# Arduino101BiomedDevBoard.net
KiCad netlist of a schematic drawn in EAGLE
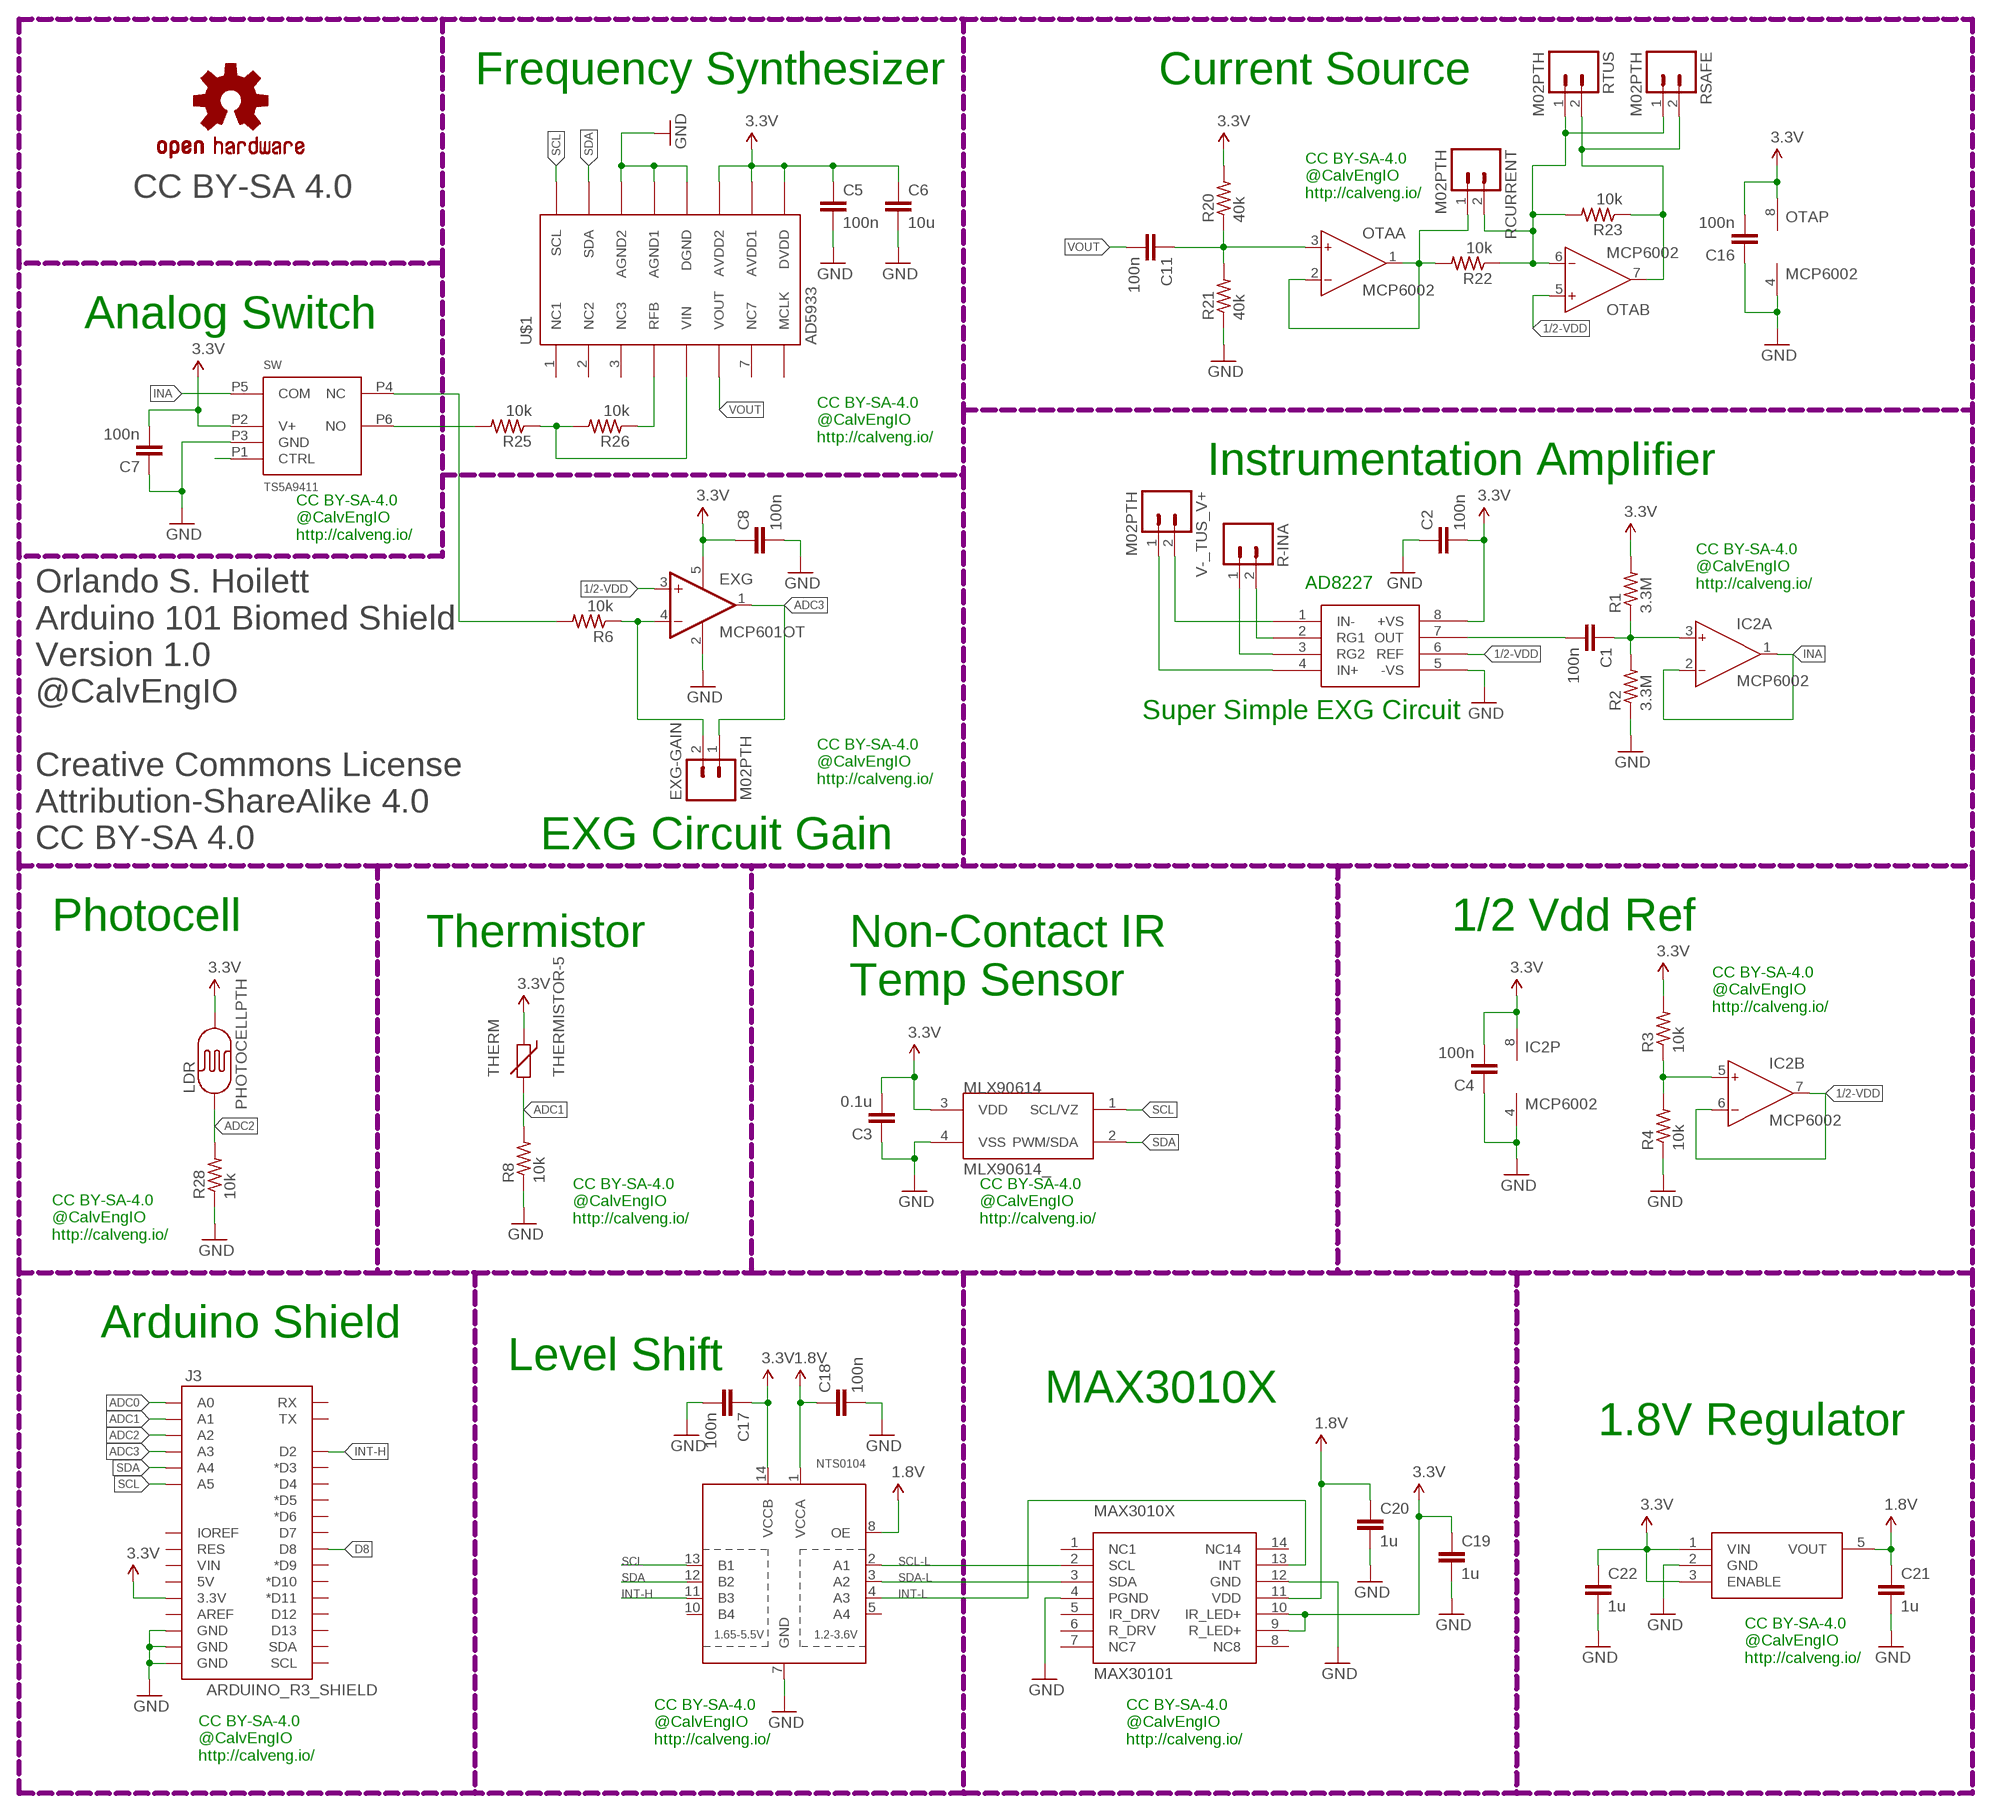
[diagram p0: schematic, sheet 1]

(export (version "E")
  (design (tool "Eeschema 10.0.6"))
  (components
    (comp (ref "1.8V")
      (value "MIC5504")
      (footprint "eagle-import:SOT23-5")
      (libsource (lib "eagle-import") (part "MIC5504"))
    )
    (comp (ref "C1")
      (value "100n")
      (footprint "eagle-import:C0402")
      (libsource (lib "eagle-import") (part "C-EUC0402"))
    )
    (comp (ref "C2")
      (value "100n")
      (footprint "eagle-import:C0402")
      (libsource (lib "eagle-import") (part "C-EUC0402"))
    )
    (comp (ref "C3")
      (value "0.1u")
      (footprint "eagle-import:C0402")
      (libsource (lib "eagle-import") (part "C-EUC0402"))
    )
    (comp (ref "C4")
      (value "100n")
      (footprint "eagle-import:C0402")
      (libsource (lib "eagle-import") (part "C-EUC0402"))
    )
    (comp (ref "C5")
      (value "100n")
      (footprint "eagle-import:C0402")
      (libsource (lib "eagle-import") (part "C-EUC0402"))
    )
    (comp (ref "C6")
      (value "10u")
      (footprint "eagle-import:C0805")
      (libsource (lib "eagle-import") (part "C-EUC0805"))
    )
    (comp (ref "C7")
      (value "100n")
      (footprint "eagle-import:C0402")
      (libsource (lib "eagle-import") (part "C-EUC0402"))
    )
    (comp (ref "C8")
      (value "100n")
      (footprint "eagle-import:C0402")
      (libsource (lib "eagle-import") (part "C-EUC0402"))
    )
    (comp (ref "C11")
      (value "100n")
      (footprint "eagle-import:C0402")
      (libsource (lib "eagle-import") (part "C-EUC0402"))
    )
    (comp (ref "C16")
      (value "100n")
      (footprint "eagle-import:C0402")
      (libsource (lib "eagle-import") (part "C-EUC0402"))
    )
    (comp (ref "C17")
      (value "100n")
      (footprint "eagle-import:C0402")
      (libsource (lib "eagle-import") (part "C-EUC0402"))
    )
    (comp (ref "C18")
      (value "100n")
      (footprint "eagle-import:C0402")
      (libsource (lib "eagle-import") (part "C-EUC0402"))
    )
    (comp (ref "C19")
      (value "1u")
      (footprint "eagle-import:C0402")
      (libsource (lib "eagle-import") (part "C-EUC0402"))
    )
    (comp (ref "C20")
      (value "1u")
      (footprint "eagle-import:C0402")
      (libsource (lib "eagle-import") (part "C-EUC0402"))
    )
    (comp (ref "C21")
      (value "1u")
      (footprint "eagle-import:C0402")
      (libsource (lib "eagle-import") (part "C-EUC0402"))
    )
    (comp (ref "C22")
      (value "1u")
      (footprint "eagle-import:C0402")
      (libsource (lib "eagle-import") (part "C-EUC0402"))
    )
    (comp (ref "EXG")
      (value "MCP601OT")
      (footprint "eagle-import:SOT23-5")
      (libsource (lib "eagle-import") (part "MCP601OT"))
    )
    (comp (ref "EXG-GAIN")
      (value "M02PTH")
      (footprint "eagle-import:1X02")
      (libsource (lib "eagle-import") (part "M02PTH"))
    )
    (comp (ref "IC2")
      (value "MCP6002")
      (footprint "eagle-import:MSOP08")
      (fields (field (name "MF") "ALTERA CORPORATION") (field (name "MPN") "AD8607ARMZ-REEL"))
      (libsource (lib "eagle-import") (part "AD8607RM"))
    )
    (comp (ref "INA")
      (value "AD8220")
      (footprint "eagle-import:MSOP08")
      (libsource (lib "eagle-import") (part "AD8220"))
    )
    (comp (ref "J3")
      (value "ARDUINO_R3_SHIELD")
      (footprint "eagle-import:UNO_R3_SHIELD")
      (libsource (lib "eagle-import") (part "ARDUINO_R3_SHIELD"))
    )
    (comp (ref "LDR")
      (value "PHOTOCELLPTH")
      (footprint "eagle-import:PHOTOCELL")
      (libsource (lib "eagle-import") (part "PHOTOCELLPTH"))
    )
    (comp (ref "LOGO3")
      (value "OSHW-LOGOM")
      (footprint "eagle-import:OSHW-LOGO-M")
      (libsource (lib "eagle-import") (part "OSHW-LOGOM"))
    )
    (comp (ref "MAX3010X")
      (value "MAX30101")
      (footprint "eagle-import:OESIP14")
      (libsource (lib "eagle-import") (part "MAX30100"))
    )
    (comp (ref "MLX90614")
      (value "MLX90614_")
      (footprint "eagle-import:TO-39")
      (libsource (lib "eagle-import") (part "MLX90614_"))
    )
    (comp (ref "NTS0104")
      (value "TXB0104PWR")
      (footprint "eagle-import:TSSOP14")
      (libsource (lib "eagle-import") (part "TXB0104PWR"))
    )
    (comp (ref "OTA")
      (value "MCP6002")
      (footprint "eagle-import:MSOP08")
      (fields (field (name "MF") "ALTERA CORPORATION") (field (name "MPN") "AD8607ARMZ-REEL"))
      (libsource (lib "eagle-import") (part "AD8607RM"))
    )
    (comp (ref "R-INA")
      (value "M02PTH")
      (footprint "eagle-import:1X02")
      (libsource (lib "eagle-import") (part "M02PTH"))
    )
    (comp (ref "R1")
      (value "3.3M")
      (footprint "eagle-import:R0402")
      (libsource (lib "eagle-import") (part "R-US_R0402"))
    )
    (comp (ref "R2")
      (value "3.3M")
      (footprint "eagle-import:R0402")
      (libsource (lib "eagle-import") (part "R-US_R0402"))
    )
    (comp (ref "R3")
      (value "10k")
      (footprint "eagle-import:R0402")
      (libsource (lib "eagle-import") (part "R-US_R0402"))
    )
    (comp (ref "R4")
      (value "10k")
      (footprint "eagle-import:R0402")
      (libsource (lib "eagle-import") (part "R-US_R0402"))
    )
    (comp (ref "R6")
      (value "10k")
      (footprint "eagle-import:R0402")
      (libsource (lib "eagle-import") (part "R-US_R0402"))
    )
    (comp (ref "R8")
      (value "10k")
      (footprint "eagle-import:R0402")
      (libsource (lib "eagle-import") (part "R-US_R0402"))
    )
    (comp (ref "R20")
      (value "40k")
      (footprint "eagle-import:R0402")
      (libsource (lib "eagle-import") (part "R-US_R0402"))
    )
    (comp (ref "R21")
      (value "40k")
      (footprint "eagle-import:R0402")
      (libsource (lib "eagle-import") (part "R-US_R0402"))
    )
    (comp (ref "R22")
      (value "10k")
      (footprint "eagle-import:R0402")
      (libsource (lib "eagle-import") (part "R-US_R0402"))
    )
    (comp (ref "R23")
      (value "10k")
      (footprint "eagle-import:R0402")
      (libsource (lib "eagle-import") (part "R-US_R0402"))
    )
    (comp (ref "R25")
      (value "10k")
      (footprint "eagle-import:R0402")
      (libsource (lib "eagle-import") (part "R-US_R0402"))
    )
    (comp (ref "R26")
      (value "10k")
      (footprint "eagle-import:R0402")
      (libsource (lib "eagle-import") (part "R-US_R0402"))
    )
    (comp (ref "R28")
      (value "10k")
      (footprint "eagle-import:R0402")
      (libsource (lib "eagle-import") (part "R-US_R0402"))
    )
    (comp (ref "RCURRENT")
      (value "M02PTH")
      (footprint "eagle-import:1X02")
      (libsource (lib "eagle-import") (part "M02PTH"))
    )
    (comp (ref "RSAFE")
      (value "M02PTH")
      (footprint "eagle-import:1X02")
      (libsource (lib "eagle-import") (part "M02PTH"))
    )
    (comp (ref "RTUS")
      (value "M02PTH")
      (footprint "eagle-import:1X02")
      (libsource (lib "eagle-import") (part "M02PTH"))
    )
    (comp (ref "SW")
      (value "TS5A9411")
      (footprint "eagle-import:SOT-363")
      (libsource (lib "eagle-import") (part "TS5A9411"))
    )
    (comp (ref "THERM")
      (value "THERMISTOR-5")
      (footprint "eagle-import:R-5")
      (libsource (lib "eagle-import") (part "THERMISTOR-5"))
    )
    (comp (ref "U$1")
      (value "AD5933")
      (footprint "eagle-import:SSOP-16")
      (libsource (lib "eagle-import") (part "AD5933"))
    )
    (comp (ref "V-_TUS_V+")
      (value "M02PTH")
      (footprint "eagle-import:1X02")
      (libsource (lib "eagle-import") (part "M02PTH"))
    )
  )
  (nets
    (net (code "1") (name "/INT-L") (class "Default")
      (node (ref "MAX3010X") (pin "13") (pinfunction "INT_13") (pintype "bidirectional"))
      (node (ref "NTS0104") (pin "4") (pinfunction "A3_4") (pintype "bidirectional"))
    )
    (net (code "2") (name "/SCL-L") (class "Default")
      (node (ref "MAX3010X") (pin "2") (pinfunction "SCL_2") (pintype "bidirectional"))
      (node (ref "NTS0104") (pin "2") (pinfunction "A1_2") (pintype "bidirectional"))
    )
    (net (code "3") (name "/SDA-L") (class "Default")
      (node (ref "MAX3010X") (pin "3") (pinfunction "SDA_3") (pintype "bidirectional"))
      (node (ref "NTS0104") (pin "3") (pinfunction "A2_3") (pintype "bidirectional"))
    )
    (net (code "4") (name "1.8V") (class "Default")
      (node (ref "1.8V") (pin "5") (pinfunction "VOUT_5") (pintype "bidirectional"))
      (node (ref "C18") (pin "1") (pinfunction "1_1") (pintype "passive"))
      (node (ref "C20") (pin "1") (pinfunction "1_1") (pintype "passive"))
      (node (ref "C21") (pin "1") (pinfunction "1_1") (pintype "passive"))
      (node (ref "MAX3010X") (pin "11") (pinfunction "VDD_11") (pintype "bidirectional"))
      (node (ref "NTS0104") (pin "1") (pinfunction "VCCA_1") (pintype "bidirectional"))
      (node (ref "NTS0104") (pin "8") (pinfunction "OE_8") (pintype "bidirectional"))
    )
    (net (code "5") (name "1{slash}2-VDD") (class "Default")
      (node (ref "EXG") (pin "3") (pinfunction "+IN_3") (pintype "input"))
      (node (ref "IC2") (pin "6") (pinfunction "IN-_6") (pintype "input"))
      (node (ref "IC2") (pin "7") (pinfunction "OUT_7") (pintype "output"))
      (node (ref "INA") (pin "6") (pinfunction "REF_6") (pintype "bidirectional"))
      (node (ref "OTA") (pin "5") (pinfunction "IN+_5") (pintype "input"))
    )
    (net (code "6") (name "3.3V") (class "Default")
      (node (ref "1.8V") (pin "1") (pinfunction "VIN_1") (pintype "bidirectional"))
      (node (ref "1.8V") (pin "3") (pinfunction "ENABLE_3") (pintype "bidirectional"))
      (node (ref "C16") (pin "2") (pinfunction "2_2") (pintype "passive"))
      (node (ref "C17") (pin "1") (pinfunction "1_1") (pintype "passive"))
      (node (ref "C19") (pin "1") (pinfunction "1_1") (pintype "passive"))
      (node (ref "C2") (pin "2") (pinfunction "2_2") (pintype "passive"))
      (node (ref "C22") (pin "1") (pinfunction "1_1") (pintype "passive"))
      (node (ref "C3") (pin "2") (pinfunction "2_2") (pintype "passive"))
      (node (ref "C4") (pin "2") (pinfunction "2_2") (pintype "passive"))
      (node (ref "C5") (pin "1") (pinfunction "1_1") (pintype "passive"))
      (node (ref "C6") (pin "1") (pinfunction "1_1") (pintype "passive"))
      (node (ref "C7") (pin "2") (pinfunction "2_2") (pintype "passive"))
      (node (ref "C8") (pin "1") (pinfunction "1_1") (pintype "passive"))
      (node (ref "EXG") (pin "5") (pinfunction "V+_5") (pintype "power_in"))
      (node (ref "IC2") (pin "8") (pinfunction "V+_8") (pintype "power_in"))
      (node (ref "INA") (pin "8") (pinfunction "+VS_8") (pintype "bidirectional"))
      (node (ref "J3") (pin "3.3V") (pinfunction "3.3V_3.3V") (pintype "bidirectional"))
      (node (ref "LDR") (pin "2") (pinfunction "P$2_2") (pintype "bidirectional"))
      (node (ref "MAX3010X") (pin "10") (pinfunction "IR_LED+_10") (pintype "bidirectional"))
      (node (ref "MAX3010X") (pin "9") (pinfunction "R_LED+_9") (pintype "bidirectional"))
      (node (ref "MLX90614") (pin "3") (pinfunction "VDD_3") (pintype "bidirectional"))
      (node (ref "NTS0104") (pin "14") (pinfunction "VCCB_14") (pintype "bidirectional"))
      (node (ref "OTA") (pin "8") (pinfunction "V+_8") (pintype "power_in"))
      (node (ref "R1") (pin "2") (pinfunction "2_2") (pintype "passive"))
      (node (ref "R20") (pin "2") (pinfunction "2_2") (pintype "passive"))
      (node (ref "R3") (pin "2") (pinfunction "2_2") (pintype "passive"))
      (node (ref "SW") (pin "P2") (pinfunction "V+_P2") (pintype "bidirectional"))
      (node (ref "THERM") (pin "1") (pinfunction "1_1") (pintype "passive"))
      (node (ref "U$1") (pin "10") (pinfunction "AVDD1_10") (pintype "bidirectional"))
      (node (ref "U$1") (pin "11") (pinfunction "AVDD2_11") (pintype "bidirectional"))
      (node (ref "U$1") (pin "9") (pinfunction "DVDD_9") (pintype "bidirectional"))
    )
    (net (code "7") (name "ADC0") (class "Default")
      (node (ref "J3") (pin "A0") (pinfunction "A0_A0") (pintype "bidirectional"))
    )
    (net (code "8") (name "ADC1") (class "Default")
      (node (ref "J3") (pin "A1") (pinfunction "A1_A1") (pintype "bidirectional"))
      (node (ref "R8") (pin "2") (pinfunction "2_2") (pintype "passive"))
      (node (ref "THERM") (pin "2") (pinfunction "2_2") (pintype "passive"))
    )
    (net (code "9") (name "ADC2") (class "Default")
      (node (ref "J3") (pin "A2") (pinfunction "A2_A2") (pintype "bidirectional"))
      (node (ref "LDR") (pin "1") (pinfunction "P$1_1") (pintype "bidirectional"))
      (node (ref "R28") (pin "2") (pinfunction "2_2") (pintype "passive"))
    )
    (net (code "10") (name "ADC3") (class "Default")
      (node (ref "EXG") (pin "1") (pinfunction "OUT_1") (pintype "output"))
      (node (ref "EXG-GAIN") (pin "1") (pinfunction "1_1") (pintype "passive"))
      (node (ref "J3") (pin "A3") (pinfunction "A3_A3") (pintype "bidirectional"))
    )
    (net (code "11") (name "D8") (class "Default")
      (node (ref "J3") (pin "D8") (pinfunction "D8_D8") (pintype "bidirectional"))
      (node (ref "SW") (pin "P1") (pinfunction "CTRL_P1") (pintype "bidirectional"))
    )
    (net (code "12") (name "GND") (class "Default")
      (node (ref "1.8V") (pin "2") (pinfunction "GND_2") (pintype "bidirectional"))
      (node (ref "C16") (pin "1") (pinfunction "1_1") (pintype "passive"))
      (node (ref "C17") (pin "2") (pinfunction "2_2") (pintype "passive"))
      (node (ref "C18") (pin "2") (pinfunction "2_2") (pintype "passive"))
      (node (ref "C19") (pin "2") (pinfunction "2_2") (pintype "passive"))
      (node (ref "C2") (pin "1") (pinfunction "1_1") (pintype "passive"))
      (node (ref "C20") (pin "2") (pinfunction "2_2") (pintype "passive"))
      (node (ref "C21") (pin "2") (pinfunction "2_2") (pintype "passive"))
      (node (ref "C22") (pin "2") (pinfunction "2_2") (pintype "passive"))
      (node (ref "C3") (pin "1") (pinfunction "1_1") (pintype "passive"))
      (node (ref "C4") (pin "1") (pinfunction "1_1") (pintype "passive"))
      (node (ref "C5") (pin "2") (pinfunction "2_2") (pintype "passive"))
      (node (ref "C6") (pin "2") (pinfunction "2_2") (pintype "passive"))
      (node (ref "C7") (pin "1") (pinfunction "1_1") (pintype "passive"))
      (node (ref "C8") (pin "2") (pinfunction "2_2") (pintype "passive"))
      (node (ref "EXG") (pin "2") (pinfunction "V-_2") (pintype "power_in"))
      (node (ref "IC2") (pin "4") (pinfunction "V-_4") (pintype "power_in"))
      (node (ref "INA") (pin "5") (pinfunction "-VS_5") (pintype "bidirectional"))
      (node (ref "J3") (pin "GND@0") (pinfunction "GND_GND@0") (pintype "bidirectional"))
      (node (ref "J3") (pin "GND@1") (pinfunction "GND_GND@1") (pintype "bidirectional"))
      (node (ref "J3") (pin "GND@2") (pinfunction "GND_GND@2") (pintype "bidirectional"))
      (node (ref "MAX3010X") (pin "12") (pinfunction "GND_12") (pintype "bidirectional"))
      (node (ref "MAX3010X") (pin "4") (pinfunction "PGND_4") (pintype "bidirectional"))
      (node (ref "MLX90614") (pin "4") (pinfunction "VSS_4") (pintype "bidirectional"))
      (node (ref "NTS0104") (pin "7") (pinfunction "GND_7") (pintype "bidirectional"))
      (node (ref "OTA") (pin "4") (pinfunction "V-_4") (pintype "power_in"))
      (node (ref "R2") (pin "1") (pinfunction "1_1") (pintype "passive"))
      (node (ref "R21") (pin "1") (pinfunction "1_1") (pintype "passive"))
      (node (ref "R28") (pin "1") (pinfunction "1_1") (pintype "passive"))
      (node (ref "R4") (pin "1") (pinfunction "1_1") (pintype "passive"))
      (node (ref "R8") (pin "1") (pinfunction "1_1") (pintype "passive"))
      (node (ref "SW") (pin "P3") (pinfunction "GND_P3") (pintype "bidirectional"))
      (node (ref "U$1") (pin "12") (pinfunction "DGND_12") (pintype "bidirectional"))
      (node (ref "U$1") (pin "13") (pinfunction "AGND1_13") (pintype "bidirectional"))
      (node (ref "U$1") (pin "14") (pinfunction "AGND2_14") (pintype "bidirectional"))
    )
    (net (code "13") (name "INA") (class "Default")
      (node (ref "IC2") (pin "1") (pinfunction "OUT_1") (pintype "output"))
      (node (ref "IC2") (pin "2") (pinfunction "IN-_2") (pintype "input"))
      (node (ref "SW") (pin "P5") (pinfunction "COM_P5") (pintype "bidirectional"))
    )
    (net (code "14") (name "INT-H") (class "Default")
      (node (ref "J3") (pin "D2") (pinfunction "D2_D2") (pintype "bidirectional"))
      (node (ref "NTS0104") (pin "11") (pinfunction "B3_11") (pintype "bidirectional"))
    )
    (net (code "15") (name "Net-(EXG--IN)") (class "Default")
      (node (ref "EXG") (pin "4") (pinfunction "-IN_4") (pintype "input"))
      (node (ref "EXG-GAIN") (pin "2") (pinfunction "2_2") (pintype "passive"))
      (node (ref "R6") (pin "1") (pinfunction "1_1") (pintype "passive"))
    )
    (net (code "16") (name "Net-(IC2A-IN+)") (class "Default")
      (node (ref "C1") (pin "1") (pinfunction "1_1") (pintype "passive"))
      (node (ref "IC2") (pin "3") (pinfunction "IN+_3") (pintype "input"))
      (node (ref "R1") (pin "1") (pinfunction "1_1") (pintype "passive"))
      (node (ref "R2") (pin "2") (pinfunction "2_2") (pintype "passive"))
    )
    (net (code "17") (name "Net-(IC2B-IN+)") (class "Default")
      (node (ref "IC2") (pin "5") (pinfunction "IN+_5") (pintype "input"))
      (node (ref "R3") (pin "1") (pinfunction "1_1") (pintype "passive"))
      (node (ref "R4") (pin "2") (pinfunction "2_2") (pintype "passive"))
    )
    (net (code "18") (name "Net-(INA-IN+)") (class "Default")
      (node (ref "INA") (pin "4") (pinfunction "IN+_4") (pintype "bidirectional"))
      (node (ref "V-_TUS_V+") (pin "1") (pinfunction "1_1") (pintype "passive"))
    )
    (net (code "19") (name "Net-(INA-IN-)") (class "Default")
      (node (ref "INA") (pin "1") (pinfunction "IN-_1") (pintype "bidirectional"))
      (node (ref "V-_TUS_V+") (pin "2") (pinfunction "2_2") (pintype "passive"))
    )
    (net (code "20") (name "Net-(INA-OUT)") (class "Default")
      (node (ref "C1") (pin "2") (pinfunction "2_2") (pintype "passive"))
      (node (ref "INA") (pin "7") (pinfunction "OUT_7") (pintype "bidirectional"))
    )
    (net (code "21") (name "Net-(INA-RG1)") (class "Default")
      (node (ref "INA") (pin "2") (pinfunction "RG1_2") (pintype "bidirectional"))
      (node (ref "R-INA") (pin "2") (pinfunction "2_2") (pintype "passive"))
    )
    (net (code "22") (name "Net-(INA-RG2)") (class "Default")
      (node (ref "INA") (pin "3") (pinfunction "RG2_3") (pintype "bidirectional"))
      (node (ref "R-INA") (pin "1") (pinfunction "1_1") (pintype "passive"))
    )
    (net (code "23") (name "Net-(OTAA-IN+)") (class "Default")
      (node (ref "C11") (pin "1") (pinfunction "1_1") (pintype "passive"))
      (node (ref "OTA") (pin "3") (pinfunction "IN+_3") (pintype "input"))
      (node (ref "R20") (pin "1") (pinfunction "1_1") (pintype "passive"))
      (node (ref "R21") (pin "2") (pinfunction "2_2") (pintype "passive"))
    )
    (net (code "24") (name "Net-(OTAA-IN-)") (class "Default")
      (node (ref "OTA") (pin "1") (pinfunction "OUT_1") (pintype "output"))
      (node (ref "OTA") (pin "2") (pinfunction "IN-_2") (pintype "input"))
      (node (ref "R22") (pin "2") (pinfunction "2_2") (pintype "passive"))
      (node (ref "RCURRENT") (pin "1") (pinfunction "1_1") (pintype "passive"))
    )
    (net (code "25") (name "Net-(OTAB-IN-)") (class "Default")
      (node (ref "OTA") (pin "6") (pinfunction "IN-_6") (pintype "input"))
      (node (ref "R22") (pin "1") (pinfunction "1_1") (pintype "passive"))
      (node (ref "R23") (pin "2") (pinfunction "2_2") (pintype "passive"))
      (node (ref "RCURRENT") (pin "2") (pinfunction "2_2") (pintype "passive"))
      (node (ref "RSAFE") (pin "1") (pinfunction "1_1") (pintype "passive"))
      (node (ref "RTUS") (pin "1") (pinfunction "1_1") (pintype "passive"))
    )
    (net (code "26") (name "Net-(OTAB-OUT)") (class "Default")
      (node (ref "OTA") (pin "7") (pinfunction "OUT_7") (pintype "output"))
      (node (ref "R23") (pin "1") (pinfunction "1_1") (pintype "passive"))
      (node (ref "RSAFE") (pin "2") (pinfunction "2_2") (pintype "passive"))
      (node (ref "RTUS") (pin "2") (pinfunction "2_2") (pintype "passive"))
    )
    (net (code "27") (name "Net-(SW-NC)") (class "Default")
      (node (ref "R6") (pin "2") (pinfunction "2_2") (pintype "passive"))
      (node (ref "SW") (pin "P4") (pinfunction "NC_P4") (pintype "bidirectional"))
    )
    (net (code "28") (name "Net-(SW-NO)") (class "Default")
      (node (ref "R25") (pin "2") (pinfunction "2_2") (pintype "passive"))
      (node (ref "SW") (pin "P6") (pinfunction "NO_P6") (pintype "bidirectional"))
    )
    (net (code "29") (name "Net-(U$1-RFB)") (class "Default")
      (node (ref "R26") (pin "1") (pinfunction "1_1") (pintype "passive"))
      (node (ref "U$1") (pin "4") (pinfunction "RFB_4") (pintype "bidirectional"))
    )
    (net (code "30") (name "Net-(U$1-VIN)") (class "Default")
      (node (ref "R25") (pin "1") (pinfunction "1_1") (pintype "passive"))
      (node (ref "R26") (pin "2") (pinfunction "2_2") (pintype "passive"))
      (node (ref "U$1") (pin "5") (pinfunction "VIN_5") (pintype "bidirectional"))
    )
    (net (code "31") (name "SCL") (class "Default")
      (node (ref "J3") (pin "A5") (pinfunction "A5_A5") (pintype "bidirectional"))
      (node (ref "MLX90614") (pin "1") (pinfunction "SCL/VZ_1") (pintype "bidirectional"))
      (node (ref "NTS0104") (pin "13") (pinfunction "B1_13") (pintype "bidirectional"))
      (node (ref "U$1") (pin "16") (pinfunction "SCL_16") (pintype "bidirectional"))
    )
    (net (code "32") (name "SDA") (class "Default")
      (node (ref "J3") (pin "A4") (pinfunction "A4_A4") (pintype "bidirectional"))
      (node (ref "MLX90614") (pin "2") (pinfunction "PWM/SDA_2") (pintype "bidirectional"))
      (node (ref "NTS0104") (pin "12") (pinfunction "B2_12") (pintype "bidirectional"))
      (node (ref "U$1") (pin "15") (pinfunction "SDA_15") (pintype "bidirectional"))
    )
    (net (code "33") (name "VOUT") (class "Default")
      (node (ref "C11") (pin "2") (pinfunction "2_2") (pintype "passive"))
      (node (ref "U$1") (pin "6") (pinfunction "VOUT_6") (pintype "bidirectional"))
    )
    (net (code "34") (name "unconnected-(J3-*D3-PadD3)") (class "Default")
      (node (ref "J3") (pin "D3") (pinfunction "*D3_D3") (pintype "bidirectional"))
    )
    (net (code "35") (name "unconnected-(J3-*D5-PadD5)") (class "Default")
      (node (ref "J3") (pin "D5") (pinfunction "*D5_D5") (pintype "bidirectional"))
    )
    (net (code "36") (name "unconnected-(J3-*D6-PadD6)") (class "Default")
      (node (ref "J3") (pin "D6") (pinfunction "*D6_D6") (pintype "bidirectional"))
    )
    (net (code "37") (name "unconnected-(J3-*D9-PadD9)") (class "Default")
      (node (ref "J3") (pin "D9") (pinfunction "*D9_D9") (pintype "bidirectional"))
    )
    (net (code "38") (name "unconnected-(J3-*D10-PadD10)") (class "Default")
      (node (ref "J3") (pin "D10") (pinfunction "*D10_D10") (pintype "bidirectional"))
    )
    (net (code "39") (name "unconnected-(J3-*D11-PadD11)") (class "Default")
      (node (ref "J3") (pin "D11") (pinfunction "*D11_D11") (pintype "bidirectional"))
    )
    (net (code "40") (name "unconnected-(J3-Pad5V)") (class "Default")
      (node (ref "J3") (pin "5V") (pinfunction "5V_5V") (pintype "bidirectional"))
    )
    (net (code "41") (name "unconnected-(J3-PadAREF)") (class "Default")
      (node (ref "J3") (pin "AREF") (pinfunction "AREF_AREF") (pintype "bidirectional"))
    )
    (net (code "42") (name "unconnected-(J3-PadD4)") (class "Default")
      (node (ref "J3") (pin "D4") (pinfunction "D4_D4") (pintype "bidirectional"))
    )
    (net (code "43") (name "unconnected-(J3-PadD7)") (class "Default")
      (node (ref "J3") (pin "D7") (pinfunction "D7_D7") (pintype "bidirectional"))
    )
    (net (code "44") (name "unconnected-(J3-PadD12)") (class "Default")
      (node (ref "J3") (pin "D12") (pinfunction "D12_D12") (pintype "bidirectional"))
    )
    (net (code "45") (name "unconnected-(J3-PadD13)") (class "Default")
      (node (ref "J3") (pin "D13") (pinfunction "D13_D13") (pintype "bidirectional"))
    )
    (net (code "46") (name "unconnected-(J3-PadIOREF)") (class "Default")
      (node (ref "J3") (pin "IOREF") (pinfunction "IOREF_IOREF") (pintype "bidirectional"))
    )
    (net (code "47") (name "unconnected-(J3-PadRES)") (class "Default")
      (node (ref "J3") (pin "RES") (pinfunction "RES_RES") (pintype "bidirectional"))
    )
    (net (code "48") (name "unconnected-(J3-PadRX)") (class "Default")
      (node (ref "J3") (pin "RX") (pinfunction "RX_RX") (pintype "bidirectional"))
    )
    (net (code "49") (name "unconnected-(J3-PadSCL)") (class "Default")
      (node (ref "J3") (pin "SCL") (pinfunction "SCL_SCL") (pintype "bidirectional"))
    )
    (net (code "50") (name "unconnected-(J3-PadSDA)") (class "Default")
      (node (ref "J3") (pin "SDA") (pinfunction "SDA_SDA") (pintype "bidirectional"))
    )
    (net (code "51") (name "unconnected-(J3-PadTX)") (class "Default")
      (node (ref "J3") (pin "TX") (pinfunction "TX_TX") (pintype "bidirectional"))
    )
    (net (code "52") (name "unconnected-(J3-PadVIN)") (class "Default")
      (node (ref "J3") (pin "VIN") (pinfunction "VIN_VIN") (pintype "bidirectional"))
    )
    (net (code "53") (name "unconnected-(MAX3010X-IR_DRV-Pad5)") (class "Default")
      (node (ref "MAX3010X") (pin "5") (pinfunction "IR_DRV_5") (pintype "bidirectional"))
    )
    (net (code "54") (name "unconnected-(MAX3010X-NC1-Pad1)") (class "Default")
      (node (ref "MAX3010X") (pin "1") (pinfunction "NC1_1") (pintype "bidirectional"))
    )
    (net (code "55") (name "unconnected-(MAX3010X-NC7-Pad7)") (class "Default")
      (node (ref "MAX3010X") (pin "7") (pinfunction "NC7_7") (pintype "bidirectional"))
    )
    (net (code "56") (name "unconnected-(MAX3010X-NC8-Pad8)") (class "Default")
      (node (ref "MAX3010X") (pin "8") (pinfunction "NC8_8") (pintype "bidirectional"))
    )
    (net (code "57") (name "unconnected-(MAX3010X-NC14-Pad14)") (class "Default")
      (node (ref "MAX3010X") (pin "14") (pinfunction "NC14_14") (pintype "bidirectional"))
    )
    (net (code "58") (name "unconnected-(MAX3010X-R_DRV-Pad6)") (class "Default")
      (node (ref "MAX3010X") (pin "6") (pinfunction "R_DRV_6") (pintype "bidirectional"))
    )
    (net (code "59") (name "unconnected-(NTS0104-A4-Pad5)") (class "Default")
      (node (ref "NTS0104") (pin "5") (pinfunction "A4_5") (pintype "bidirectional"))
    )
    (net (code "60") (name "unconnected-(NTS0104-B4-Pad10)") (class "Default")
      (node (ref "NTS0104") (pin "10") (pinfunction "B4_10") (pintype "bidirectional"))
    )
    (net (code "61") (name "unconnected-(U$1-MCLK-Pad8)") (class "Default")
      (node (ref "U$1") (pin "8") (pinfunction "MCLK_8") (pintype "bidirectional"))
    )
    (net (code "62") (name "unconnected-(U$1-NC1-Pad1)") (class "Default")
      (node (ref "U$1") (pin "1") (pinfunction "NC1_1") (pintype "bidirectional"))
    )
    (net (code "63") (name "unconnected-(U$1-NC2-Pad2)") (class "Default")
      (node (ref "U$1") (pin "2") (pinfunction "NC2_2") (pintype "bidirectional"))
    )
    (net (code "64") (name "unconnected-(U$1-NC3-Pad3)") (class "Default")
      (node (ref "U$1") (pin "3") (pinfunction "NC3_3") (pintype "bidirectional"))
    )
    (net (code "65") (name "unconnected-(U$1-NC7-Pad7)") (class "Default")
      (node (ref "U$1") (pin "7") (pinfunction "NC7_7") (pintype "bidirectional"))
    )
  )
)
